# Sheet1.net
KiCad netlist of a schematic drawn in Altium Designer
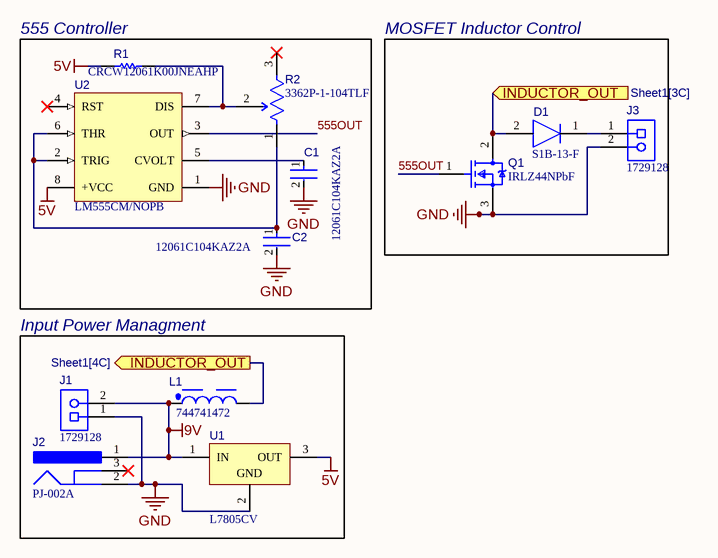
[diagram p0: Sheet1.SchDoc]

(export (version "E")
  (design (tool "Eeschema 10.0.6"))
  (components
    (comp (ref "C1")
      (value "12061C104KAZ2A")
      (footprint "FP-1206-L_3_2_0_2-W_1_6_0-MFG")
      (description "General Purpose Ceramic Capacitor, 1206, 100nF, 10%, X7R, 15%, 100V")
      (fields (field (name "TOLERANCE") "10%"))
      (libsource (lib "Altium Content Vault") (part "b4654b650e69147ec39a6b967a45e02"))
    )
    (comp (ref "C2")
      (value "12061C104KAZ2A")
      (footprint "FP-1206-L_3_2_0_2-W_1_6_0-MFG")
      (description "General Purpose Ceramic Capacitor, 1206, 100nF, 10%, X7R, 15%, 100V")
      (fields (field (name "TOLERANCE") "10%"))
      (libsource (lib "Altium Content Vault") (part "b4654b650e69147ec39a6b967a45e02"))
    )
    (comp (ref "D1")
      (value "S1B-13-F")
      (footprint "FP-SMA-MFG")
      (description "DIODE GEN PURP 100V 1A SMA")
      (libsource (lib "Altium Content Vault") (part "03cb15f8d8994b06d21941eb207504f"))
    )
    (comp (ref "J1")
      (value "1729128")
      (footprint "PHOE-1729128-2_V")
      (description "PCB Terminal Block, 13.5 A, 400 V, 2-Pin THD, RoHS, Bulk")
      (fields (field (name "MANUFACTURER") "Phoenix Contact"))
      (libsource (lib "Altium Content Vault") (part "CN-2P-F-R2"))
    )
    (comp (ref "J2")
      (value "PJ-002A")
      (footprint "CUI-PJ-002A_V")
      (fields (field (name "MANUFACTURER") "CUIInc."))
      (libsource (lib "Altium Content Vault") (part "JACK-2CD3-RN_B"))
    )
    (comp (ref "J3")
      (value "1729128")
      (footprint "PHOE-1729128-2_V")
      (description "PCB Terminal Block, 13.5 A, 400 V, 2-Pin THD, RoHS, Bulk")
      (fields (field (name "MANUFACTURER") "Phoenix Contact"))
      (libsource (lib "") (part "CN-2P-F-R2_1"))
    )
    (comp (ref "L1")
      (value "744741472")
      (footprint "WE-TI_8055")
      (fields (field (name "TOLERANCE") "10%"))
      (libsource (lib "Altium Content Vault") (part "Inductor - 2"))
    )
    (comp (ref "Q1")
      (value "IRLZ44NPbF")
      (footprint "FP-PG-TO220-3-MFG")
      (description "MOSFET N-CH 55V 47A TO220AB")
      (libsource (lib "Altium Content Vault") (part "b09f7f152735e370c1ea22a33fa83d6"))
    )
    (comp (ref "R1")
      (value "CRCW12061K00JNEAHP")
      (footprint "RESC3116X65X50LL20T20")
      (fields (field (name "MANUFACTURER") "Vishay Dale"))
      (libsource (lib "Altium Content Vault") (part "RES"))
    )
    (comp (ref "R2")
      (value "3362P-1-104TLF")
      (footprint "FP-3362P-T-MFG")
      (description "TRIMMER 100K OHM 0.5W PC PIN TOP")
      (fields (field (name "TOLERANCE") "10%"))
      (libsource (lib "Altium Content Vault") (part "13357d81287629c2fd191d242cfa50c"))
    )
    (comp (ref "U1")
      (value "L7805CV")
      (footprint "TO220")
      (description "Positive Voltage Regulator, 5V, 3-Pin TO-220")
      (libsource (lib "Altium Content Vault") (part "PM-REG-L4940-SIL3"))
    )
    (comp (ref "U2")
      (value "LM555CM/NOPB")
      (footprint "D0008A_M")
      (description "Timer, 8-pin Narrow SOIC, Pb-Free")
      (fields (field (name "MANUFACTURER") "Texas Instruments"))
      (libsource (lib "Altium Content Vault") (part "AN-TIMER-LM555-8"))
    )
  )
  (nets
    (net (code "1") (name "/555OUT") (class "Default")
      (node (ref "Q1") (pin "1") (pinfunction "G_1") (pintype "passive"))
      (node (ref "U2") (pin "3") (pinfunction "OUT_3") (pintype "output"))
    )
    (net (code "2") (name "/INDUCTOR_OUT") (class "Default")
      (node (ref "D1") (pin "2") (pinfunction "A_2") (pintype "passive"))
      (node (ref "L1") (pin "2") (pinfunction "2_2") (pintype "passive"))
      (node (ref "Q1") (pin "2") (pinfunction "D_2") (pintype "passive"))
    )
    (net (code "3") (name "5V") (class "Default")
      (node (ref "R1") (pin "1") (pinfunction "1_1") (pintype "passive"))
      (node (ref "U1") (pin "3") (pinfunction "OUT_3") (pintype "power_in"))
      (node (ref "U2") (pin "8") (pinfunction "+VCC_8") (pintype "power_in"))
    )
    (net (code "4") (name "9V") (class "Default")
      (node (ref "J1") (pin "2") (pinfunction "2_2") (pintype "passive"))
      (node (ref "J2") (pin "1") (pinfunction "1_1") (pintype "passive"))
      (node (ref "L1") (pin "1") (pinfunction "1_1") (pintype "passive"))
      (node (ref "U1") (pin "1") (pinfunction "IN_1") (pintype "power_in"))
    )
    (net (code "5") (name "GND") (class "Default")
      (node (ref "C1") (pin "2") (pinfunction "2_2") (pintype "passive"))
      (node (ref "C2") (pin "2") (pinfunction "2_2") (pintype "passive"))
      (node (ref "J1") (pin "1") (pinfunction "1_1") (pintype "passive"))
      (node (ref "J2") (pin "2") (pinfunction "2_2") (pintype "passive"))
      (node (ref "J3") (pin "2") (pinfunction "2_2") (pintype "passive"))
      (node (ref "Q1") (pin "3") (pinfunction "S_3") (pintype "passive"))
      (node (ref "U1") (pin "2") (pinfunction "GND_2") (pintype "power_in"))
      (node (ref "U2") (pin "1") (pinfunction "GND_1") (pintype "power_in"))
    )
    (net (code "6") (name "Net-(D1-C)") (class "Default")
      (node (ref "D1") (pin "1") (pinfunction "C_1") (pintype "passive"))
      (node (ref "J3") (pin "1") (pinfunction "1_1") (pintype "passive"))
    )
    (net (code "7") (name "Net-(R2-CCW)") (class "Default")
      (node (ref "C2") (pin "1") (pinfunction "1_1") (pintype "passive"))
      (node (ref "R2") (pin "1") (pinfunction "CCW_1") (pintype "passive"))
      (node (ref "U2") (pin "2") (pinfunction "TRIG_2") (pintype "input"))
      (node (ref "U2") (pin "6") (pinfunction "THR_6") (pintype "input"))
    )
    (net (code "8") (name "Net-(R2-WIPER)") (class "Default")
      (node (ref "R1") (pin "2") (pinfunction "2_2") (pintype "passive"))
      (node (ref "R2") (pin "2") (pinfunction "WIPER_2") (pintype "passive"))
      (node (ref "U2") (pin "7") (pinfunction "DIS_7") (pintype "open_collector"))
    )
    (net (code "9") (name "Net-(U2-CVOLT)") (class "Default")
      (node (ref "C1") (pin "1") (pinfunction "1_1") (pintype "passive"))
      (node (ref "U2") (pin "5") (pinfunction "CVOLT_5") (pintype "passive"))
    )
    (net (code "10") (name "unconnected-(J2-Pad3)") (class "Default")
      (node (ref "J2") (pin "3") (pinfunction "3_3") (pintype "passive+no_connect"))
    )
    (net (code "11") (name "unconnected-(R2-CW-Pad3)") (class "Default")
      (node (ref "R2") (pin "3") (pinfunction "CW_3") (pintype "passive+no_connect"))
    )
    (net (code "12") (name "unconnected-(U2-RST-Pad4)") (class "Default")
      (node (ref "U2") (pin "4") (pinfunction "RST_4") (pintype "input+no_connect"))
    )
  )
)
